# univ_3-2-4-x-rev2-1coil.net
KiCad netlist of a schematic drawn in EAGLE
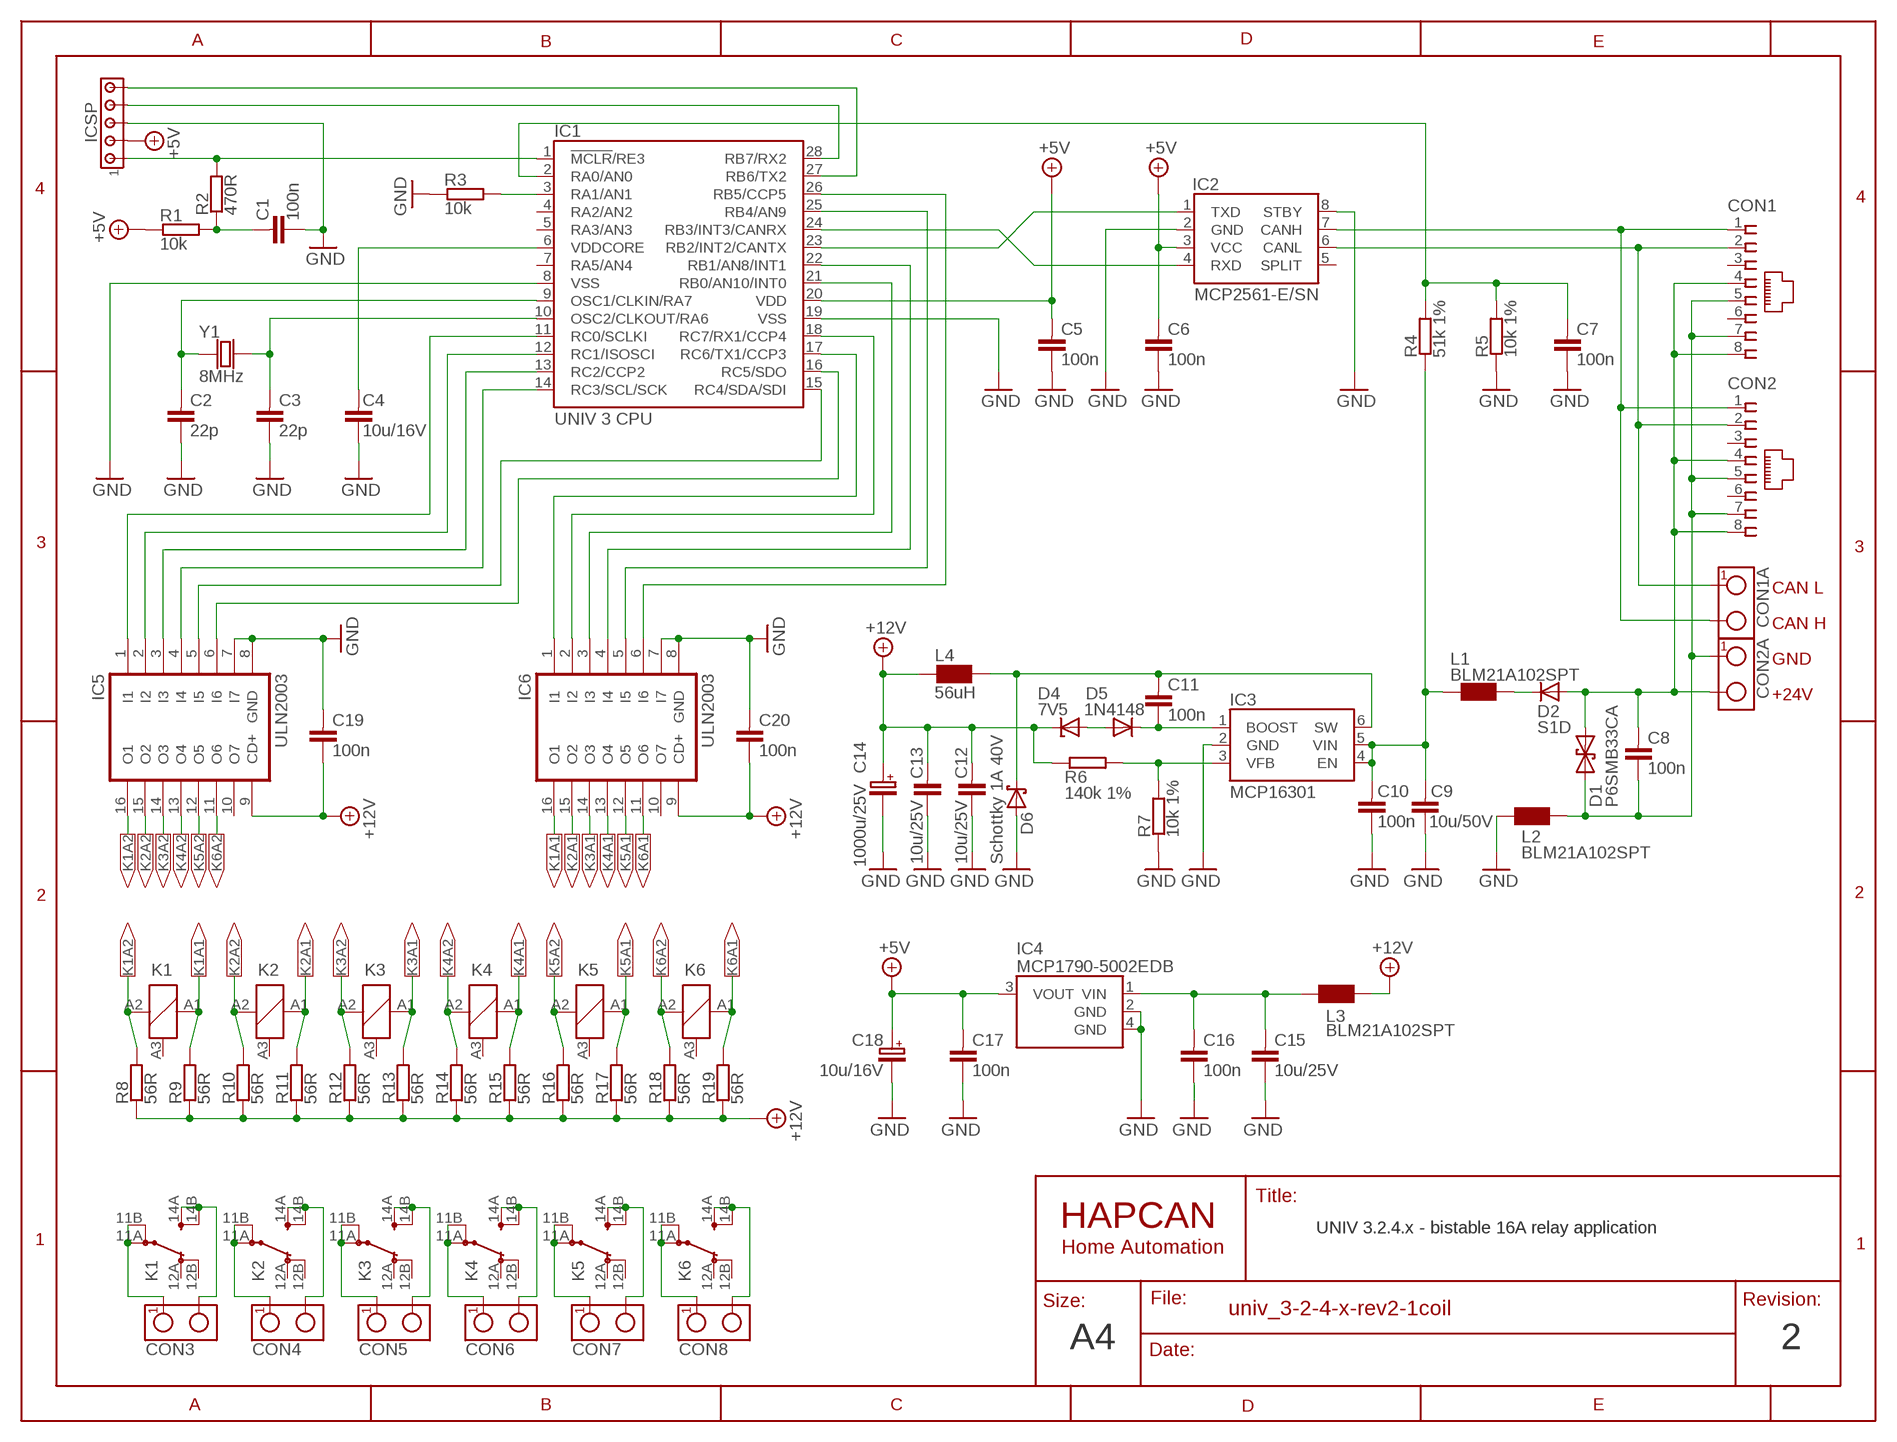
[diagram p0: schematic, sheet 1]

(export (version "E")
  (design (tool "Eeschema 10.0.6"))
  (components
    (comp (ref "C1")
      (value "100n")
      (footprint "eagle-import:0805")
      (libsource (lib "eagle-import") (part "CAPACITOR0805"))
    )
    (comp (ref "C2")
      (value "22p")
      (footprint "eagle-import:0805")
      (libsource (lib "eagle-import") (part "CAPACITOR0805"))
    )
    (comp (ref "C3")
      (value "22p")
      (footprint "eagle-import:0805")
      (libsource (lib "eagle-import") (part "CAPACITOR0805"))
    )
    (comp (ref "C4")
      (value "10u/16V")
      (footprint "eagle-import:0805")
      (libsource (lib "eagle-import") (part "CAPACITOR0805"))
    )
    (comp (ref "C5")
      (value "100n")
      (footprint "eagle-import:0805")
      (libsource (lib "eagle-import") (part "CAPACITOR0805"))
    )
    (comp (ref "C6")
      (value "100n")
      (footprint "eagle-import:0805")
      (libsource (lib "eagle-import") (part "CAPACITOR0805"))
    )
    (comp (ref "C7")
      (value "100n")
      (footprint "eagle-import:0805")
      (libsource (lib "eagle-import") (part "CAPACITOR0805"))
    )
    (comp (ref "C8")
      (value "100n")
      (footprint "eagle-import:0805")
      (libsource (lib "eagle-import") (part "CAPACITOR0805"))
    )
    (comp (ref "C9")
      (value "10u/50V")
      (footprint "eagle-import:1210")
      (libsource (lib "eagle-import") (part "CAPACITOR1210"))
    )
    (comp (ref "C10")
      (value "100n")
      (footprint "eagle-import:0805")
      (libsource (lib "eagle-import") (part "CAPACITOR0805"))
    )
    (comp (ref "C11")
      (value "100n")
      (footprint "eagle-import:0805")
      (libsource (lib "eagle-import") (part "CAPACITOR0805"))
    )
    (comp (ref "C12")
      (value "10u/25V")
      (footprint "eagle-import:1206")
      (libsource (lib "eagle-import") (part "CAPACITOR1206"))
    )
    (comp (ref "C13")
      (value "10u/25V")
      (footprint "eagle-import:1206")
      (libsource (lib "eagle-import") (part "CAPACITOR1206"))
    )
    (comp (ref "C14")
      (value "1000u/25V")
      (footprint "eagle-import:CAP-5X10.5")
      (libsource (lib "eagle-import") (part "CAPACITOR-POLARIZED-5X10.5"))
    )
    (comp (ref "C15")
      (value "10u/25V")
      (footprint "eagle-import:1206")
      (libsource (lib "eagle-import") (part "CAPACITOR1206"))
    )
    (comp (ref "C16")
      (value "100n")
      (footprint "eagle-import:0805")
      (libsource (lib "eagle-import") (part "CAPACITOR0805"))
    )
    (comp (ref "C17")
      (value "100n")
      (footprint "eagle-import:0805")
      (libsource (lib "eagle-import") (part "CAPACITOR0805"))
    )
    (comp (ref "C18")
      (value "10u/16V")
      (footprint "eagle-import:SMC_B")
      (libsource (lib "eagle-import") (part "CAPACITOR-POLARIZED-SMC_B"))
    )
    (comp (ref "C19")
      (value "100n")
      (footprint "eagle-import:0805")
      (libsource (lib "eagle-import") (part "CAPACITOR0805"))
    )
    (comp (ref "C20")
      (value "100n")
      (footprint "eagle-import:0805")
      (libsource (lib "eagle-import") (part "CAPACITOR0805"))
    )
    (comp (ref "CON1")
      (value "RJ45-SOCKET")
      (footprint "eagle-import:RJ45-PCB-SOCKET")
      (libsource (lib "eagle-import") (part "RJ45-SOCKET"))
    )
    (comp (ref "CON1A")
      (value "TERMINAL-2")
      (footprint "eagle-import:ARK2-5X10,5MM")
      (libsource (lib "eagle-import") (part "TERMINAL-2-5X10,5MM"))
    )
    (comp (ref "CON2")
      (value "RJ45-SOCKET")
      (footprint "eagle-import:RJ45-PCB-SOCKET")
      (libsource (lib "eagle-import") (part "RJ45-SOCKET"))
    )
    (comp (ref "CON2A")
      (value "TERMINAL-2")
      (footprint "eagle-import:ARK2-5X10,5MM")
      (libsource (lib "eagle-import") (part "TERMINAL-2-5X10,5MM"))
    )
    (comp (ref "CON3")
      (value "TERMINAL-2")
      (footprint "eagle-import:ARK2-7.5X10.5MM")
      (libsource (lib "eagle-import") (part "TERMINAL-2-7.5X10.5MM"))
    )
    (comp (ref "CON4")
      (value "TERMINAL-2")
      (footprint "eagle-import:ARK2-7.5X10.5MM")
      (libsource (lib "eagle-import") (part "TERMINAL-2-7.5X10.5MM"))
    )
    (comp (ref "CON5")
      (value "TERMINAL-2")
      (footprint "eagle-import:ARK2-7.5X10.5MM")
      (libsource (lib "eagle-import") (part "TERMINAL-2-7.5X10.5MM"))
    )
    (comp (ref "CON6")
      (value "TERMINAL-2")
      (footprint "eagle-import:ARK2-7.5X10.5MM")
      (libsource (lib "eagle-import") (part "TERMINAL-2-7.5X10.5MM"))
    )
    (comp (ref "CON7")
      (value "TERMINAL-2")
      (footprint "eagle-import:ARK2-7.5X10.5MM")
      (libsource (lib "eagle-import") (part "TERMINAL-2-7.5X10.5MM"))
    )
    (comp (ref "CON8")
      (value "TERMINAL-2")
      (footprint "eagle-import:ARK2-7.5X10.5MM")
      (libsource (lib "eagle-import") (part "TERMINAL-2-7.5X10.5MM"))
    )
    (comp (ref "D1")
      (value "P6SMB33CA")
      (footprint "eagle-import:DO-214_TRANSIL2")
      (libsource (lib "eagle-import") (part "DIODE_TRANSIL2"))
    )
    (comp (ref "D2")
      (value "S1D")
      (footprint "eagle-import:DO-214")
      (libsource (lib "eagle-import") (part "DIODE_DO-214"))
    )
    (comp (ref "D4")
      (value "7V5")
      (footprint "eagle-import:SOD-80")
      (libsource (lib "eagle-import") (part "DIODE_ZENER_SOD-80"))
    )
    (comp (ref "D5")
      (value "1N4148")
      (footprint "eagle-import:0805")
      (libsource (lib "eagle-import") (part "DIODE_0805"))
    )
    (comp (ref "D6")
      (value "Schottky 1A 40V")
      (footprint "eagle-import:DO-214")
      (libsource (lib "eagle-import") (part "DIODE_TRANSIL1_DO214"))
    )
    (comp (ref "IC1")
      (value "UNIV 3 CPU")
      (footprint "eagle-import:UNIV3CPU")
      (libsource (lib "eagle-import") (part "UNIV3CPU-I/SO"))
    )
    (comp (ref "IC2")
      (value "MCP2561-E/SN")
      (footprint "eagle-import:SO-08")
      (libsource (lib "eagle-import") (part "MCP2561-E/SN"))
    )
    (comp (ref "IC3")
      (value "MCP16301")
      (footprint "eagle-import:SOT-23-6")
      (libsource (lib "eagle-import") (part "MCP16301SOT23-6"))
    )
    (comp (ref "IC4")
      (value "MCP1790-5002EDB")
      (footprint "eagle-import:SOT-223")
      (libsource (lib "eagle-import") (part "MCP1826SOT223-3"))
    )
    (comp (ref "IC5")
      (value "ULN2003")
      (footprint "eagle-import:SO-16")
      (libsource (lib "eagle-import") (part "ULN2003"))
    )
    (comp (ref "IC6")
      (value "ULN2003")
      (footprint "eagle-import:SO-16")
      (libsource (lib "eagle-import") (part "ULN2003"))
    )
    (comp (ref "ICSP")
      (value "HEADER5")
      (footprint "eagle-import:SIP-5")
      (libsource (lib "eagle-import") (part "HEADER5"))
    )
    (comp (ref "K1")
      (value "RELAY_RT")
      (footprint "eagle-import:RELAY_RT")
      (libsource (lib "eagle-import") (part "RELAY_RT"))
    )
    (comp (ref "K2")
      (value "RELAY_RT")
      (footprint "eagle-import:RELAY_RT")
      (libsource (lib "eagle-import") (part "RELAY_RT"))
    )
    (comp (ref "K3")
      (value "RELAY_RT")
      (footprint "eagle-import:RELAY_RT")
      (libsource (lib "eagle-import") (part "RELAY_RT"))
    )
    (comp (ref "K4")
      (value "RELAY_RT")
      (footprint "eagle-import:RELAY_RT")
      (libsource (lib "eagle-import") (part "RELAY_RT"))
    )
    (comp (ref "K5")
      (value "RELAY_RT")
      (footprint "eagle-import:RELAY_RT")
      (libsource (lib "eagle-import") (part "RELAY_RT"))
    )
    (comp (ref "K6")
      (value "RELAY_RT")
      (footprint "eagle-import:RELAY_RT")
      (libsource (lib "eagle-import") (part "RELAY_RT"))
    )
    (comp (ref "L1")
      (value "BLM21A102SPT")
      (footprint "eagle-import:0805")
      (libsource (lib "eagle-import") (part "CHOKE0805"))
    )
    (comp (ref "L2")
      (value "BLM21A102SPT")
      (footprint "eagle-import:0805")
      (libsource (lib "eagle-import") (part "CHOKE0805"))
    )
    (comp (ref "L3")
      (value "BLM21A102SPT")
      (footprint "eagle-import:0805")
      (libsource (lib "eagle-import") (part "CHOKE0805"))
    )
    (comp (ref "L4")
      (value "56uH")
      (footprint "eagle-import:CHOKE-DER0705")
      (libsource (lib "eagle-import") (part "CHOKEDER0705"))
    )
    (comp (ref "R1")
      (value "10k")
      (footprint "eagle-import:0805")
      (libsource (lib "eagle-import") (part "RESISTOR0805"))
    )
    (comp (ref "R2")
      (value "470R")
      (footprint "eagle-import:0805")
      (libsource (lib "eagle-import") (part "RESISTOR0805"))
    )
    (comp (ref "R3")
      (value "10k")
      (footprint "eagle-import:0805")
      (libsource (lib "eagle-import") (part "RESISTOR0805"))
    )
    (comp (ref "R4")
      (value "51k 1%")
      (footprint "eagle-import:0805")
      (libsource (lib "eagle-import") (part "RESISTOR0805"))
    )
    (comp (ref "R5")
      (value "10k 1%")
      (footprint "eagle-import:0805")
      (libsource (lib "eagle-import") (part "RESISTOR0805"))
    )
    (comp (ref "R6")
      (value "140k 1%")
      (footprint "eagle-import:0805")
      (libsource (lib "eagle-import") (part "RESISTOR0805"))
    )
    (comp (ref "R7")
      (value "10k 1%")
      (footprint "eagle-import:0805")
      (libsource (lib "eagle-import") (part "RESISTOR0805"))
    )
    (comp (ref "R8")
      (value "56R")
      (footprint "eagle-import:1206")
      (libsource (lib "eagle-import") (part "RESISTOR1206"))
    )
    (comp (ref "R9")
      (value "56R")
      (footprint "eagle-import:1206")
      (libsource (lib "eagle-import") (part "RESISTOR1206"))
    )
    (comp (ref "R10")
      (value "56R")
      (footprint "eagle-import:1206")
      (libsource (lib "eagle-import") (part "RESISTOR1206"))
    )
    (comp (ref "R11")
      (value "56R")
      (footprint "eagle-import:1206")
      (libsource (lib "eagle-import") (part "RESISTOR1206"))
    )
    (comp (ref "R12")
      (value "56R")
      (footprint "eagle-import:1206")
      (libsource (lib "eagle-import") (part "RESISTOR1206"))
    )
    (comp (ref "R13")
      (value "56R")
      (footprint "eagle-import:1206")
      (libsource (lib "eagle-import") (part "RESISTOR1206"))
    )
    (comp (ref "R14")
      (value "56R")
      (footprint "eagle-import:1206")
      (libsource (lib "eagle-import") (part "RESISTOR1206"))
    )
    (comp (ref "R15")
      (value "56R")
      (footprint "eagle-import:1206")
      (libsource (lib "eagle-import") (part "RESISTOR1206"))
    )
    (comp (ref "R16")
      (value "56R")
      (footprint "eagle-import:1206")
      (libsource (lib "eagle-import") (part "RESISTOR1206"))
    )
    (comp (ref "R17")
      (value "56R")
      (footprint "eagle-import:1206")
      (libsource (lib "eagle-import") (part "RESISTOR1206"))
    )
    (comp (ref "R18")
      (value "56R")
      (footprint "eagle-import:1206")
      (libsource (lib "eagle-import") (part "RESISTOR1206"))
    )
    (comp (ref "R19")
      (value "56R")
      (footprint "eagle-import:1206")
      (libsource (lib "eagle-import") (part "RESISTOR1206"))
    )
    (comp (ref "Y1")
      (value "8MHz")
      (footprint "eagle-import:CRYSTAL-HC49V")
      (libsource (lib "eagle-import") (part "CRYSTAL-HC49V"))
    )
  )
  (nets
    (net (code "1") (name "+5V") (class "Default")
      (node (ref "C17") (pin "1") (pinfunction "1_1") (pintype "passive"))
      (node (ref "C18") (pin "+") (pinfunction "1_+") (pintype "passive"))
      (node (ref "C5") (pin "1") (pinfunction "1_1") (pintype "passive"))
      (node (ref "C6") (pin "1") (pinfunction "1_1") (pintype "passive"))
      (node (ref "IC1") (pin "20") (pinfunction "VDD_20") (pintype "bidirectional"))
      (node (ref "IC2") (pin "3") (pinfunction "VCC_3") (pintype "bidirectional"))
      (node (ref "IC4") (pin "3") (pinfunction "VOUT_3") (pintype "bidirectional"))
      (node (ref "ICSP") (pin "2") (pinfunction "2_2") (pintype "passive"))
      (node (ref "R1") (pin "1") (pinfunction "1_1") (pintype "passive"))
    )
    (net (code "2") (name "+12V") (class "Default")
      (node (ref "C12") (pin "1") (pinfunction "1_1") (pintype "passive"))
      (node (ref "C13") (pin "1") (pinfunction "1_1") (pintype "passive"))
      (node (ref "C14") (pin "+") (pinfunction "1_+") (pintype "passive"))
      (node (ref "C19") (pin "2") (pinfunction "2_2") (pintype "passive"))
      (node (ref "C20") (pin "2") (pinfunction "2_2") (pintype "passive"))
      (node (ref "D4") (pin "C") (pinfunction "C_C") (pintype "passive"))
      (node (ref "IC5") (pin "9") (pinfunction "CD+_9") (pintype "passive"))
      (node (ref "IC6") (pin "9") (pinfunction "CD+_9") (pintype "passive"))
      (node (ref "L3") (pin "2") (pinfunction "2_2") (pintype "passive"))
      (node (ref "L4") (pin "1") (pinfunction "1_1") (pintype "passive"))
      (node (ref "R10") (pin "1") (pinfunction "1_1") (pintype "passive"))
      (node (ref "R11") (pin "1") (pinfunction "1_1") (pintype "passive"))
      (node (ref "R12") (pin "1") (pinfunction "1_1") (pintype "passive"))
      (node (ref "R13") (pin "1") (pinfunction "1_1") (pintype "passive"))
      (node (ref "R14") (pin "1") (pinfunction "1_1") (pintype "passive"))
      (node (ref "R15") (pin "1") (pinfunction "1_1") (pintype "passive"))
      (node (ref "R16") (pin "1") (pinfunction "1_1") (pintype "passive"))
      (node (ref "R17") (pin "1") (pinfunction "1_1") (pintype "passive"))
      (node (ref "R18") (pin "1") (pinfunction "1_1") (pintype "passive"))
      (node (ref "R19") (pin "1") (pinfunction "1_1") (pintype "passive"))
      (node (ref "R6") (pin "1") (pinfunction "1_1") (pintype "passive"))
      (node (ref "R8") (pin "1") (pinfunction "1_1") (pintype "passive"))
      (node (ref "R9") (pin "1") (pinfunction "1_1") (pintype "passive"))
    )
    (net (code "3") (name "/K1A1") (class "Default")
      (node (ref "IC6") (pin "16") (pinfunction "O1_16") (pintype "open_collector"))
      (node (ref "K1") (pin "A1") (pinfunction "S+_A1") (pintype "passive"))
      (node (ref "R9") (pin "2") (pinfunction "2_2") (pintype "passive"))
    )
    (net (code "4") (name "/K1A2") (class "Default")
      (node (ref "IC5") (pin "16") (pinfunction "O1_16") (pintype "open_collector"))
      (node (ref "K1") (pin "A2") (pinfunction "R+_A2") (pintype "passive"))
      (node (ref "R8") (pin "2") (pinfunction "2_2") (pintype "passive"))
    )
    (net (code "5") (name "/K2A1") (class "Default")
      (node (ref "IC6") (pin "15") (pinfunction "O2_15") (pintype "open_collector"))
      (node (ref "K2") (pin "A1") (pinfunction "S+_A1") (pintype "passive"))
      (node (ref "R11") (pin "2") (pinfunction "2_2") (pintype "passive"))
    )
    (net (code "6") (name "/K2A2") (class "Default")
      (node (ref "IC5") (pin "15") (pinfunction "O2_15") (pintype "open_collector"))
      (node (ref "K2") (pin "A2") (pinfunction "R+_A2") (pintype "passive"))
      (node (ref "R10") (pin "2") (pinfunction "2_2") (pintype "passive"))
    )
    (net (code "7") (name "/K3A1") (class "Default")
      (node (ref "IC6") (pin "14") (pinfunction "O3_14") (pintype "open_collector"))
      (node (ref "K3") (pin "A1") (pinfunction "S+_A1") (pintype "passive"))
      (node (ref "R13") (pin "2") (pinfunction "2_2") (pintype "passive"))
    )
    (net (code "8") (name "/K3A2") (class "Default")
      (node (ref "IC5") (pin "14") (pinfunction "O3_14") (pintype "open_collector"))
      (node (ref "K3") (pin "A2") (pinfunction "R+_A2") (pintype "passive"))
      (node (ref "R12") (pin "2") (pinfunction "2_2") (pintype "passive"))
    )
    (net (code "9") (name "/K4A1") (class "Default")
      (node (ref "IC6") (pin "13") (pinfunction "O4_13") (pintype "open_collector"))
      (node (ref "K4") (pin "A1") (pinfunction "S+_A1") (pintype "passive"))
      (node (ref "R15") (pin "2") (pinfunction "2_2") (pintype "passive"))
    )
    (net (code "10") (name "/K4A2") (class "Default")
      (node (ref "IC5") (pin "13") (pinfunction "O4_13") (pintype "open_collector"))
      (node (ref "K4") (pin "A2") (pinfunction "R+_A2") (pintype "passive"))
      (node (ref "R14") (pin "2") (pinfunction "2_2") (pintype "passive"))
    )
    (net (code "11") (name "/K5A1") (class "Default")
      (node (ref "IC6") (pin "12") (pinfunction "O5_12") (pintype "open_collector"))
      (node (ref "K5") (pin "A1") (pinfunction "S+_A1") (pintype "passive"))
      (node (ref "R17") (pin "2") (pinfunction "2_2") (pintype "passive"))
    )
    (net (code "12") (name "/K5A2") (class "Default")
      (node (ref "IC5") (pin "12") (pinfunction "O5_12") (pintype "open_collector"))
      (node (ref "K5") (pin "A2") (pinfunction "R+_A2") (pintype "passive"))
      (node (ref "R16") (pin "2") (pinfunction "2_2") (pintype "passive"))
    )
    (net (code "13") (name "/K6A1") (class "Default")
      (node (ref "IC6") (pin "11") (pinfunction "O6_11") (pintype "open_collector"))
      (node (ref "K6") (pin "A1") (pinfunction "S+_A1") (pintype "passive"))
      (node (ref "R19") (pin "2") (pinfunction "2_2") (pintype "passive"))
    )
    (net (code "14") (name "/K6A2") (class "Default")
      (node (ref "IC5") (pin "11") (pinfunction "O6_11") (pintype "open_collector"))
      (node (ref "K6") (pin "A2") (pinfunction "R+_A2") (pintype "passive"))
      (node (ref "R18") (pin "2") (pinfunction "2_2") (pintype "passive"))
    )
    (net (code "15") (name "GND") (class "Default")
      (node (ref "C1") (pin "2") (pinfunction "2_2") (pintype "passive"))
      (node (ref "C10") (pin "2") (pinfunction "2_2") (pintype "passive"))
      (node (ref "C12") (pin "2") (pinfunction "2_2") (pintype "passive"))
      (node (ref "C13") (pin "2") (pinfunction "2_2") (pintype "passive"))
      (node (ref "C14") (pin "-") (pinfunction "2_-") (pintype "passive"))
      (node (ref "C15") (pin "2") (pinfunction "2_2") (pintype "passive"))
      (node (ref "C16") (pin "2") (pinfunction "2_2") (pintype "passive"))
      (node (ref "C17") (pin "2") (pinfunction "2_2") (pintype "passive"))
      (node (ref "C18") (pin "-") (pinfunction "2_-") (pintype "passive"))
      (node (ref "C19") (pin "1") (pinfunction "1_1") (pintype "passive"))
      (node (ref "C2") (pin "2") (pinfunction "2_2") (pintype "passive"))
      (node (ref "C20") (pin "1") (pinfunction "1_1") (pintype "passive"))
      (node (ref "C3") (pin "2") (pinfunction "2_2") (pintype "passive"))
      (node (ref "C4") (pin "2") (pinfunction "2_2") (pintype "passive"))
      (node (ref "C5") (pin "2") (pinfunction "2_2") (pintype "passive"))
      (node (ref "C6") (pin "2") (pinfunction "2_2") (pintype "passive"))
      (node (ref "C7") (pin "2") (pinfunction "2_2") (pintype "passive"))
      (node (ref "C9") (pin "2") (pinfunction "2_2") (pintype "passive"))
      (node (ref "D6") (pin "A") (pinfunction "A_A") (pintype "passive"))
      (node (ref "IC1") (pin "19") (pinfunction "VSS_19") (pintype "bidirectional"))
      (node (ref "IC1") (pin "8") (pinfunction "VSS_8") (pintype "bidirectional"))
      (node (ref "IC2") (pin "2") (pinfunction "GND_2") (pintype "bidirectional"))
      (node (ref "IC2") (pin "8") (pinfunction "STBY_8") (pintype "bidirectional"))
      (node (ref "IC3") (pin "2") (pinfunction "GND_2") (pintype "bidirectional"))
      (node (ref "IC4") (pin "2") (pinfunction "GND_2") (pintype "bidirectional"))
      (node (ref "IC4") (pin "4") (pinfunction "GND_4") (pintype "bidirectional"))
      (node (ref "IC5") (pin "7") (pinfunction "I7_7") (pintype "input"))
      (node (ref "IC5") (pin "8") (pinfunction "GND_8") (pintype "power_in"))
      (node (ref "IC6") (pin "7") (pinfunction "I7_7") (pintype "input"))
      (node (ref "IC6") (pin "8") (pinfunction "GND_8") (pintype "power_in"))
      (node (ref "ICSP") (pin "3") (pinfunction "3_3") (pintype "passive"))
      (node (ref "L2") (pin "1") (pinfunction "1_1") (pintype "passive"))
      (node (ref "R3") (pin "1") (pinfunction "1_1") (pintype "passive"))
      (node (ref "R5") (pin "1") (pinfunction "1_1") (pintype "passive"))
      (node (ref "R7") (pin "1") (pinfunction "1_1") (pintype "passive"))
    )
    (net (code "16") (name "Net-(C1-Pad1)") (class "Default")
      (node (ref "C1") (pin "1") (pinfunction "1_1") (pintype "passive"))
      (node (ref "R1") (pin "2") (pinfunction "2_2") (pintype "passive"))
      (node (ref "R2") (pin "1") (pinfunction "1_1") (pintype "passive"))
    )
    (net (code "17") (name "Net-(D1-1)") (class "Default")
      (node (ref "C8") (pin "2") (pinfunction "2_2") (pintype "passive"))
      (node (ref "CON1") (pin "5") (pinfunction "5_5") (pintype "passive"))
      (node (ref "CON1") (pin "7") (pinfunction "7_7") (pintype "passive"))
      (node (ref "CON2") (pin "5") (pinfunction "5_5") (pintype "passive"))
      (node (ref "CON2") (pin "7") (pinfunction "7_7") (pintype "passive"))
      (node (ref "CON2A") (pin "1") (pinfunction "1_1") (pintype "passive"))
      (node (ref "D1") (pin "A") (pinfunction "1_A") (pintype "passive"))
      (node (ref "L2") (pin "2") (pinfunction "2_2") (pintype "passive"))
    )
    (net (code "18") (name "Net-(D1-2)") (class "Default")
      (node (ref "C8") (pin "1") (pinfunction "1_1") (pintype "passive"))
      (node (ref "CON1") (pin "4") (pinfunction "4_4") (pintype "passive"))
      (node (ref "CON1") (pin "8") (pinfunction "8_8") (pintype "passive"))
      (node (ref "CON2") (pin "4") (pinfunction "4_4") (pintype "passive"))
      (node (ref "CON2") (pin "8") (pinfunction "8_8") (pintype "passive"))
      (node (ref "CON2A") (pin "2") (pinfunction "2_2") (pintype "passive"))
      (node (ref "D1") (pin "C") (pinfunction "2_C") (pintype "passive"))
      (node (ref "D2") (pin "A") (pinfunction "A_A") (pintype "passive"))
    )
    (net (code "19") (name "Net-(D2-PadC)") (class "Default")
      (node (ref "D2") (pin "C") (pinfunction "C_C") (pintype "passive"))
      (node (ref "L1") (pin "2") (pinfunction "2_2") (pintype "passive"))
    )
    (net (code "20") (name "Net-(D5-A)") (class "Default")
      (node (ref "D4") (pin "A") (pinfunction "A_A") (pintype "passive"))
      (node (ref "D5") (pin "2") (pinfunction "A_2") (pintype "passive"))
    )
    (net (code "21") (name "Net-(D5-C)") (class "Default")
      (node (ref "C11") (pin "2") (pinfunction "2_2") (pintype "passive"))
      (node (ref "D5") (pin "1") (pinfunction "C_1") (pintype "passive"))
      (node (ref "IC3") (pin "1") (pinfunction "BOOST_1") (pintype "bidirectional"))
    )
    (net (code "22") (name "Net-(IC1-OSC1{slash}CLKIN{slash}RA7)") (class "Default")
      (node (ref "C2") (pin "1") (pinfunction "1_1") (pintype "passive"))
      (node (ref "IC1") (pin "9") (pinfunction "OSC1/CLKIN/RA7_9") (pintype "bidirectional"))
      (node (ref "Y1") (pin "1") (pinfunction "1_1") (pintype "passive"))
    )
    (net (code "23") (name "Net-(IC1-OSC2{slash}CLKOUT{slash}RA6)") (class "Default")
      (node (ref "C3") (pin "1") (pinfunction "1_1") (pintype "passive"))
      (node (ref "IC1") (pin "10") (pinfunction "OSC2/CLKOUT/RA6_10") (pintype "bidirectional"))
      (node (ref "Y1") (pin "2") (pinfunction "2_2") (pintype "passive"))
    )
    (net (code "24") (name "Net-(IC1-RA0{slash}AN0)") (class "Default")
      (node (ref "C7") (pin "1") (pinfunction "1_1") (pintype "passive"))
      (node (ref "IC1") (pin "2") (pinfunction "RA0/AN0_2") (pintype "bidirectional"))
      (node (ref "R4") (pin "2") (pinfunction "2_2") (pintype "passive"))
      (node (ref "R5") (pin "2") (pinfunction "2_2") (pintype "passive"))
    )
    (net (code "25") (name "Net-(IC1-RA1{slash}AN1)") (class "Default")
      (node (ref "IC1") (pin "3") (pinfunction "RA1/AN1_3") (pintype "bidirectional"))
      (node (ref "R3") (pin "2") (pinfunction "2_2") (pintype "passive"))
    )
    (net (code "26") (name "Net-(IC1-RB0{slash}AN10{slash}INT0)") (class "Default")
      (node (ref "IC1") (pin "21") (pinfunction "RB0/AN10/INT0_21") (pintype "bidirectional"))
      (node (ref "IC6") (pin "3") (pinfunction "I3_3") (pintype "input"))
    )
    (net (code "27") (name "Net-(IC1-RB1{slash}AN8{slash}INT1)") (class "Default")
      (node (ref "IC1") (pin "22") (pinfunction "RB1/AN8/INT1_22") (pintype "bidirectional"))
      (node (ref "IC6") (pin "4") (pinfunction "I4_4") (pintype "input"))
    )
    (net (code "28") (name "Net-(IC1-RB2{slash}INT2{slash}CANTX)") (class "Default")
      (node (ref "IC1") (pin "23") (pinfunction "RB2/INT2/CANTX_23") (pintype "bidirectional"))
      (node (ref "IC2") (pin "1") (pinfunction "TXD_1") (pintype "bidirectional"))
    )
    (net (code "29") (name "Net-(IC1-RB3{slash}INT3{slash}CANRX)") (class "Default")
      (node (ref "IC1") (pin "24") (pinfunction "RB3/INT3/CANRX_24") (pintype "bidirectional"))
      (node (ref "IC2") (pin "4") (pinfunction "RXD_4") (pintype "bidirectional"))
    )
    (net (code "30") (name "Net-(IC1-RB4{slash}AN9)") (class "Default")
      (node (ref "IC1") (pin "25") (pinfunction "RB4/AN9_25") (pintype "bidirectional"))
      (node (ref "IC6") (pin "5") (pinfunction "I5_5") (pintype "input"))
    )
    (net (code "31") (name "Net-(IC1-RB5{slash}CCP5)") (class "Default")
      (node (ref "IC1") (pin "26") (pinfunction "RB5/CCP5_26") (pintype "bidirectional"))
      (node (ref "IC6") (pin "6") (pinfunction "I6_6") (pintype "input"))
    )
    (net (code "32") (name "Net-(IC1-RB6{slash}TX2)") (class "Default")
      (node (ref "IC1") (pin "27") (pinfunction "RB6/TX2_27") (pintype "bidirectional"))
      (node (ref "ICSP") (pin "5") (pinfunction "5_5") (pintype "passive"))
    )
    (net (code "33") (name "Net-(IC1-RB7{slash}RX2)") (class "Default")
      (node (ref "IC1") (pin "28") (pinfunction "RB7/RX2_28") (pintype "bidirectional"))
      (node (ref "ICSP") (pin "4") (pinfunction "4_4") (pintype "passive"))
    )
    (net (code "34") (name "Net-(IC1-RC0{slash}SCLKI)") (class "Default")
      (node (ref "IC1") (pin "11") (pinfunction "RC0/SCLKI_11") (pintype "bidirectional"))
      (node (ref "IC5") (pin "1") (pinfunction "I1_1") (pintype "input"))
    )
    (net (code "35") (name "Net-(IC1-RC1{slash}ISOSCI)") (class "Default")
      (node (ref "IC1") (pin "12") (pinfunction "RC1/ISOSCI_12") (pintype "bidirectional"))
      (node (ref "IC5") (pin "2") (pinfunction "I2_2") (pintype "input"))
    )
    (net (code "36") (name "Net-(IC1-RC2{slash}CCP2)") (class "Default")
      (node (ref "IC1") (pin "13") (pinfunction "RC2/CCP2_13") (pintype "bidirectional"))
      (node (ref "IC5") (pin "3") (pinfunction "I3_3") (pintype "input"))
    )
    (net (code "37") (name "Net-(IC1-RC3{slash}SCL{slash}SCK)") (class "Default")
      (node (ref "IC1") (pin "14") (pinfunction "RC3/SCL/SCK_14") (pintype "bidirectional"))
      (node (ref "IC5") (pin "4") (pinfunction "I4_4") (pintype "input"))
    )
    (net (code "38") (name "Net-(IC1-RC4{slash}SDA{slash}SDI)") (class "Default")
      (node (ref "IC1") (pin "15") (pinfunction "RC4/SDA/SDI_15") (pintype "bidirectional"))
      (node (ref "IC5") (pin "5") (pinfunction "I5_5") (pintype "input"))
    )
    (net (code "39") (name "Net-(IC1-RC5{slash}SDO)") (class "Default")
      (node (ref "IC1") (pin "16") (pinfunction "RC5/SDO_16") (pintype "bidirectional"))
      (node (ref "IC5") (pin "6") (pinfunction "I6_6") (pintype "input"))
    )
    (net (code "40") (name "Net-(IC1-RC6{slash}TX1{slash}CCP3)") (class "Default")
      (node (ref "IC1") (pin "17") (pinfunction "RC6/TX1/CCP3_17") (pintype "bidirectional"))
      (node (ref "IC6") (pin "1") (pinfunction "I1_1") (pintype "input"))
    )
    (net (code "41") (name "Net-(IC1-RC7{slash}RX1{slash}CCP4)") (class "Default")
      (node (ref "IC1") (pin "18") (pinfunction "RC7/RX1/CCP4_18") (pintype "bidirectional"))
      (node (ref "IC6") (pin "2") (pinfunction "I2_2") (pintype "input"))
    )
    (net (code "42") (name "Net-(IC1-VDDCORE)") (class "Default")
      (node (ref "C4") (pin "1") (pinfunction "1_1") (pintype "passive"))
      (node (ref "IC1") (pin "6") (pinfunction "VDDCORE_6") (pintype "bidirectional"))
    )
    (net (code "43") (name "Net-(IC1-~{MCLR}{slash}RE3)") (class "Default")
      (node (ref "IC1") (pin "1") (pinfunction "~{MCLR}/RE3_1") (pintype "bidirectional"))
      (node (ref "ICSP") (pin "1") (pinfunction "1_1") (pintype "passive"))
      (node (ref "R2") (pin "2") (pinfunction "2_2") (pintype "passive"))
    )
    (net (code "44") (name "Net-(IC2-CANH)") (class "Default")
      (node (ref "CON1") (pin "1") (pinfunction "1_1") (pintype "passive"))
      (node (ref "CON1A") (pin "2") (pinfunction "2_2") (pintype "passive"))
      (node (ref "CON2") (pin "1") (pinfunction "1_1") (pintype "passive"))
      (node (ref "IC2") (pin "7") (pinfunction "CANH_7") (pintype "bidirectional"))
    )
    (net (code "45") (name "Net-(IC2-CANL)") (class "Default")
      (node (ref "CON1") (pin "2") (pinfunction "2_2") (pintype "passive"))
      (node (ref "CON1A") (pin "1") (pinfunction "1_1") (pintype "passive"))
      (node (ref "CON2") (pin "2") (pinfunction "2_2") (pintype "passive"))
      (node (ref "IC2") (pin "6") (pinfunction "CANL_6") (pintype "bidirectional"))
    )
    (net (code "46") (name "Net-(IC3-EN)") (class "Default")
      (node (ref "C10") (pin "1") (pinfunction "1_1") (pintype "passive"))
      (node (ref "C9") (pin "1") (pinfunction "1_1") (pintype "passive"))
      (node (ref "IC3") (pin "4") (pinfunction "EN_4") (pintype "bidirectional"))
      (node (ref "IC3") (pin "5") (pinfunction "VIN_5") (pintype "bidirectional"))
      (node (ref "L1") (pin "1") (pinfunction "1_1") (pintype "passive"))
      (node (ref "R4") (pin "1") (pinfunction "1_1") (pintype "passive"))
    )
    (net (code "47") (name "Net-(IC3-SW)") (class "Default")
      (node (ref "C11") (pin "1") (pinfunction "1_1") (pintype "passive"))
      (node (ref "D6") (pin "C") (pinfunction "C_C") (pintype "passive"))
      (node (ref "IC3") (pin "6") (pinfunction "SW_6") (pintype "bidirectional"))
      (node (ref "L4") (pin "2") (pinfunction "2_2") (pintype "passive"))
    )
    (net (code "48") (name "Net-(IC3-VFB)") (class "Default")
      (node (ref "IC3") (pin "3") (pinfunction "VFB_3") (pintype "bidirectional"))
      (node (ref "R6") (pin "2") (pinfunction "2_2") (pintype "passive"))
      (node (ref "R7") (pin "2") (pinfunction "2_2") (pintype "passive"))
    )
    (net (code "49") (name "Net-(IC4-VIN)") (class "Default")
      (node (ref "C15") (pin "1") (pinfunction "1_1") (pintype "passive"))
      (node (ref "C16") (pin "1") (pinfunction "1_1") (pintype "passive"))
      (node (ref "IC4") (pin "1") (pinfunction "VIN_1") (pintype "bidirectional"))
      (node (ref "L3") (pin "1") (pinfunction "1_1") (pintype "passive"))
    )
    (net (code "50") (name "Net-(K1A-PA)") (class "Default")
      (node (ref "CON3") (pin "1") (pinfunction "1_1") (pintype "passive"))
      (node (ref "K1") (pin "11A") (pinfunction "PA_11A") (pintype "passive"))
      (node (ref "K1") (pin "11B") (pinfunction "PB_11B") (pintype "passive"))
    )
    (net (code "51") (name "Net-(K1A-SA)") (class "Default")
      (node (ref "CON3") (pin "2") (pinfunction "2_2") (pintype "passive"))
      (node (ref "K1") (pin "14A") (pinfunction "SA_14A") (pintype "passive"))
      (node (ref "K1") (pin "14B") (pinfunction "SB_14B") (pintype "passive"))
    )
    (net (code "52") (name "Net-(K2A-PA)") (class "Default")
      (node (ref "CON4") (pin "1") (pinfunction "1_1") (pintype "passive"))
      (node (ref "K2") (pin "11A") (pinfunction "PA_11A") (pintype "passive"))
      (node (ref "K2") (pin "11B") (pinfunction "PB_11B") (pintype "passive"))
    )
    (net (code "53") (name "Net-(K2A-SA)") (class "Default")
      (node (ref "CON4") (pin "2") (pinfunction "2_2") (pintype "passive"))
      (node (ref "K2") (pin "14A") (pinfunction "SA_14A") (pintype "passive"))
      (node (ref "K2") (pin "14B") (pinfunction "SB_14B") (pintype "passive"))
    )
    (net (code "54") (name "Net-(K3A-PA)") (class "Default")
      (node (ref "CON5") (pin "1") (pinfunction "1_1") (pintype "passive"))
      (node (ref "K3") (pin "11A") (pinfunction "PA_11A") (pintype "passive"))
      (node (ref "K3") (pin "11B") (pinfunction "PB_11B") (pintype "passive"))
    )
    (net (code "55") (name "Net-(K3A-SA)") (class "Default")
      (node (ref "CON5") (pin "2") (pinfunction "2_2") (pintype "passive"))
      (node (ref "K3") (pin "14A") (pinfunction "SA_14A") (pintype "passive"))
      (node (ref "K3") (pin "14B") (pinfunction "SB_14B") (pintype "passive"))
    )
    (net (code "56") (name "Net-(K4A-PA)") (class "Default")
      (node (ref "CON6") (pin "1") (pinfunction "1_1") (pintype "passive"))
      (node (ref "K4") (pin "11A") (pinfunction "PA_11A") (pintype "passive"))
      (node (ref "K4") (pin "11B") (pinfunction "PB_11B") (pintype "passive"))
    )
    (net (code "57") (name "Net-(K4A-SA)") (class "Default")
      (node (ref "CON6") (pin "2") (pinfunction "2_2") (pintype "passive"))
      (node (ref "K4") (pin "14A") (pinfunction "SA_14A") (pintype "passive"))
      (node (ref "K4") (pin "14B") (pinfunction "SB_14B") (pintype "passive"))
    )
    (net (code "58") (name "Net-(K5A-PA)") (class "Default")
      (node (ref "CON7") (pin "1") (pinfunction "1_1") (pintype "passive"))
      (node (ref "K5") (pin "11A") (pinfunction "PA_11A") (pintype "passive"))
      (node (ref "K5") (pin "11B") (pinfunction "PB_11B") (pintype "passive"))
    )
    (net (code "59") (name "Net-(K5A-SA)") (class "Default")
      (node (ref "CON7") (pin "2") (pinfunction "2_2") (pintype "passive"))
      (node (ref "K5") (pin "14A") (pinfunction "SA_14A") (pintype "passive"))
      (node (ref "K5") (pin "14B") (pinfunction "SB_14B") (pintype "passive"))
    )
    (net (code "60") (name "Net-(K6A-PA)") (class "Default")
      (node (ref "CON8") (pin "1") (pinfunction "1_1") (pintype "passive"))
      (node (ref "K6") (pin "11A") (pinfunction "PA_11A") (pintype "passive"))
      (node (ref "K6") (pin "11B") (pinfunction "PB_11B") (pintype "passive"))
    )
    (net (code "61") (name "Net-(K6A-SA)") (class "Default")
      (node (ref "CON8") (pin "2") (pinfunction "2_2") (pintype "passive"))
      (node (ref "K6") (pin "14A") (pinfunction "SA_14A") (pintype "passive"))
      (node (ref "K6") (pin "14B") (pinfunction "SB_14B") (pintype "passive"))
    )
    (net (code "62") (name "unconnected-(CON1-Pad3)") (class "Default")
      (node (ref "CON1") (pin "3") (pinfunction "3_3") (pintype "passive"))
    )
    (net (code "63") (name "unconnected-(CON1-Pad6)") (class "Default")
      (node (ref "CON1") (pin "6") (pinfunction "6_6") (pintype "passive"))
    )
    (net (code "64") (name "unconnected-(CON2-Pad3)") (class "Default")
      (node (ref "CON2") (pin "3") (pinfunction "3_3") (pintype "passive"))
    )
    (net (code "65") (name "unconnected-(CON2-Pad6)") (class "Default")
      (node (ref "CON2") (pin "6") (pinfunction "6_6") (pintype "passive"))
    )
    (net (code "66") (name "unconnected-(IC1-RA2{slash}AN2-Pad4)") (class "Default")
      (node (ref "IC1") (pin "4") (pinfunction "RA2/AN2_4") (pintype "bidirectional"))
    )
    (net (code "67") (name "unconnected-(IC1-RA3{slash}AN3-Pad5)") (class "Default")
      (node (ref "IC1") (pin "5") (pinfunction "RA3/AN3_5") (pintype "bidirectional"))
    )
    (net (code "68") (name "unconnected-(IC1-RA5{slash}AN4-Pad7)") (class "Default")
      (node (ref "IC1") (pin "7") (pinfunction "RA5/AN4_7") (pintype "bidirectional"))
    )
    (net (code "69") (name "unconnected-(IC2-SPLIT-Pad5)") (class "Default")
      (node (ref "IC2") (pin "5") (pinfunction "SPLIT_5") (pintype "bidirectional"))
    )
    (net (code "70") (name "unconnected-(IC5-O7-Pad10)") (class "Default")
      (node (ref "IC5") (pin "10") (pinfunction "O7_10") (pintype "open_collector"))
    )
    (net (code "71") (name "unconnected-(IC6-O7-Pad10)") (class "Default")
      (node (ref "IC6") (pin "10") (pinfunction "O7_10") (pintype "open_collector"))
    )
    (net (code "72") (name "unconnected-(K1A-OA-Pad12A)") (class "Default")
      (node (ref "K1") (pin "12A") (pinfunction "OA_12A") (pintype "passive"))
    )
    (net (code "73") (name "unconnected-(K1A-OB-Pad12B)") (class "Default")
      (node (ref "K1") (pin "12B") (pinfunction "OB_12B") (pintype "passive"))
    )
    (net (code "74") (name "unconnected-(K1B---PadA3)") (class "Default")
      (node (ref "K1") (pin "A3") (pinfunction "-_A3") (pintype "passive"))
    )
    (net (code "75") (name "unconnected-(K2A-OA-Pad12A)") (class "Default")
      (node (ref "K2") (pin "12A") (pinfunction "OA_12A") (pintype "passive"))
    )
    (net (code "76") (name "unconnected-(K2A-OB-Pad12B)") (class "Default")
      (node (ref "K2") (pin "12B") (pinfunction "OB_12B") (pintype "passive"))
    )
    (net (code "77") (name "unconnected-(K2B---PadA3)") (class "Default")
      (node (ref "K2") (pin "A3") (pinfunction "-_A3") (pintype "passive"))
    )
    (net (code "78") (name "unconnected-(K3A-OA-Pad12A)") (class "Default")
      (node (ref "K3") (pin "12A") (pinfunction "OA_12A") (pintype "passive"))
    )
    (net (code "79") (name "unconnected-(K3A-OB-Pad12B)") (class "Default")
      (node (ref "K3") (pin "12B") (pinfunction "OB_12B") (pintype "passive"))
    )
    (net (code "80") (name "unconnected-(K3B---PadA3)") (class "Default")
      (node (ref "K3") (pin "A3") (pinfunction "-_A3") (pintype "passive"))
    )
    (net (code "81") (name "unconnected-(K4A-OA-Pad12A)") (class "Default")
      (node (ref "K4") (pin "12A") (pinfunction "OA_12A") (pintype "passive"))
    )
    (net (code "82") (name "unconnected-(K4A-OB-Pad12B)") (class "Default")
      (node (ref "K4") (pin "12B") (pinfunction "OB_12B") (pintype "passive"))
    )
    (net (code "83") (name "unconnected-(K4B---PadA3)") (class "Default")
      (node (ref "K4") (pin "A3") (pinfunction "-_A3") (pintype "passive"))
    )
    (net (code "84") (name "unconnected-(K5A-OA-Pad12A)") (class "Default")
      (node (ref "K5") (pin "12A") (pinfunction "OA_12A") (pintype "passive"))
    )
    (net (code "85") (name "unconnected-(K5A-OB-Pad12B)") (class "Default")
      (node (ref "K5") (pin "12B") (pinfunction "OB_12B") (pintype "passive"))
    )
    (net (code "86") (name "unconnected-(K5B---PadA3)") (class "Default")
      (node (ref "K5") (pin "A3") (pinfunction "-_A3") (pintype "passive"))
    )
    (net (code "87") (name "unconnected-(K6A-OA-Pad12A)") (class "Default")
      (node (ref "K6") (pin "12A") (pinfunction "OA_12A") (pintype "passive"))
    )
    (net (code "88") (name "unconnected-(K6A-OB-Pad12B)") (class "Default")
      (node (ref "K6") (pin "12B") (pinfunction "OB_12B") (pintype "passive"))
    )
    (net (code "89") (name "unconnected-(K6B---PadA3)") (class "Default")
      (node (ref "K6") (pin "A3") (pinfunction "-_A3") (pintype "passive"))
    )
  )
)
